# 04_-_USB-UART.net
KiCad netlist of a schematic drawn in Altium Designer
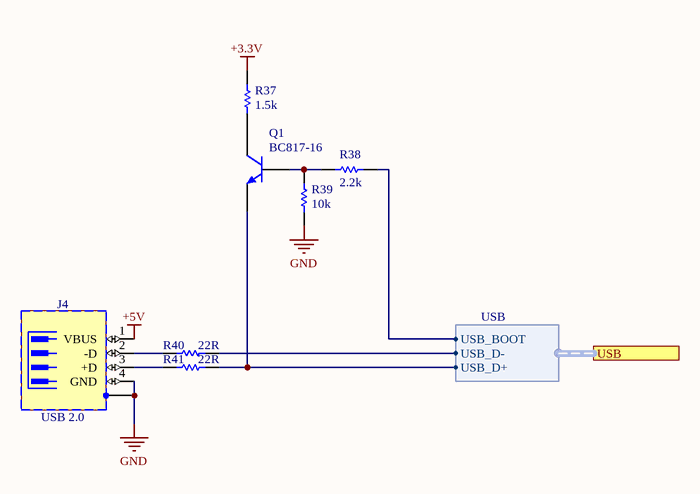
[diagram p0: [04] - USB-UART.SchDoc]

(export (version "E")
  (design (tool "Eeschema 10.0.6"))
  (components
    (comp (ref "J4")
      (value "USB 2.0")
      (footprint "WURTH_614 104 150 121")
      (description "4 Pin + 1 Shield USB Receptacle")
      (fields
        (field (name "PART NUMBER") "WURTH_614 104 150 121")
        (field (name "MANUFACTURER") "WURTH ELEKTRONIK")
        (field (name "AUTHOR") "CERN DEM JMW")
      )
      (libsource (lib "Connectors") (part "Connector USB 4 Pin + 1Shield"))
    )
    (comp (ref "Q1")
      (value "BC817-16")
      (footprint "SOT23-3")
      (description "NPN General-purpose Transistor")
      (fields
        (field (name "MANUFACTURER") "ON Semiconductor")
        (field (name "MANUFACTURER PART NUMBER") "BC817-16LT3G")
      )
      (libsource (lib "Philips Discrete BJT - Low Power") (part "BC817-16"))
    )
    (comp (ref "R37")
      (value "Res1")
      (footprint "Res-0603")
      (description "Chip Resistor")
      (fields
        (field (name "MANUFACTURER") "Panasonic")
        (field (name "MANUFACTURER PART NUMBER") "ERJ-3EKF1501V")
        (field (name "RESISTANCE") "1.5k")
      )
      (libsource (lib "Altium_Library") (part "Res1"))
    )
    (comp (ref "R38")
      (value "Res1")
      (footprint "Res-0603")
      (description "Chip Resistor")
      (fields
        (field (name "MANUFACTURER") "Panasonic")
        (field (name "MANUFACTURER PART NUMBER") "ERJ-3GEYJ222V")
        (field (name "RESISTANCE") "2.2k")
      )
      (libsource (lib "Altium_Library") (part "Res1"))
    )
    (comp (ref "R39")
      (value "Res1")
      (footprint "Res-0603")
      (description "Chip Resistor")
      (fields
        (field (name "MANUFACTURER") "Panasonic")
        (field (name "MANUFACTURER PART NUMBER") "ERJ-3GEYJ103V")
        (field (name "RESISTANCE") "10k")
      )
      (libsource (lib "Altium_Library") (part "Res1"))
    )
    (comp (ref "R40")
      (value "Res1")
      (footprint "Res-0603")
      (description "Chip Resistor")
      (fields
        (field (name "MANUFACTURER") "Panasonic")
        (field (name "MANUFACTURER PART NUMBER") "ERJ-3GEYJ220V")
        (field (name "RESISTANCE") "22R")
      )
      (libsource (lib "Altium_Library") (part "Res1"))
    )
    (comp (ref "R41")
      (value "Res1")
      (footprint "Res-0603")
      (description "Chip Resistor")
      (fields
        (field (name "MANUFACTURER") "Panasonic")
        (field (name "MANUFACTURER PART NUMBER") "ERJ-3GEYJ220V")
        (field (name "RESISTANCE") "22R")
      )
      (libsource (lib "Altium_Library") (part "Res1"))
    )
  )
  (nets
    (net (code "2") (name "+3.3V") (class "Default")
      (node (ref "R37") (pin "1") (pinfunction "1_1") (pintype "passive"))
    )
    (net (code "3") (name "+5V") (class "Default")
      (node (ref "J4") (pin "1") (pinfunction "VBUS_1") (pintype "bidirectional"))
    )
    (net (code "4") (name "/USB_BOOT") (class "Default")
      (node (ref "R38") (pin "2") (pinfunction "2_2") (pintype "passive"))
    )
    (net (code "5") (name "/USB_D+") (class "Default")
      (node (ref "Q1") (pin "2") (pinfunction "E_2") (pintype "passive"))
      (node (ref "R41") (pin "1") (pinfunction "1_1") (pintype "passive"))
    )
    (net (code "6") (name "/USB_D-") (class "Default")
      (node (ref "R40") (pin "1") (pinfunction "1_1") (pintype "passive"))
    )
    (net (code "8") (name "GND") (class "Default")
      (node (ref "J4") (pin "4") (pinfunction "GND_4") (pintype "bidirectional"))
      (node (ref "J4") (pin "5") (pinfunction "SHIELD_5") (pintype "power_in"))
      (node (ref "R39") (pin "1") (pinfunction "1_1") (pintype "passive"))
    )
    (net (code "9") (name "Net-(J4-+D)") (class "Default")
      (node (ref "J4") (pin "3") (pinfunction "+D_3") (pintype "bidirectional"))
      (node (ref "R41") (pin "2") (pinfunction "2_2") (pintype "passive"))
    )
    (net (code "10") (name "Net-(J4--D)") (class "Default")
      (node (ref "J4") (pin "2") (pinfunction "-D_2") (pintype "bidirectional"))
      (node (ref "R40") (pin "2") (pinfunction "2_2") (pintype "passive"))
    )
    (net (code "11") (name "Net-(Q1-B)") (class "Default")
      (node (ref "Q1") (pin "1") (pinfunction "B_1") (pintype "passive"))
      (node (ref "R38") (pin "1") (pinfunction "1_1") (pintype "passive"))
      (node (ref "R39") (pin "2") (pinfunction "2_2") (pintype "passive"))
    )
    (net (code "12") (name "Net-(Q1-C)") (class "Default")
      (node (ref "Q1") (pin "3") (pinfunction "C_3") (pintype "passive"))
      (node (ref "R37") (pin "2") (pinfunction "2_2") (pintype "passive"))
    )
  )
)
